# TMP37_0603.net
KiCad netlist of a schematic drawn in EAGLE
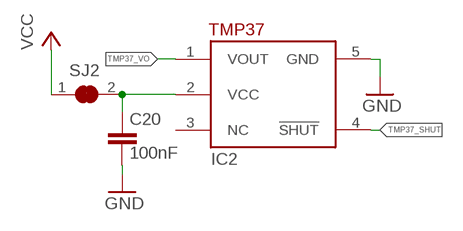
[diagram p0: schematic, sheet 1]

(export (version "E")
  (design (tool "Eeschema 10.0.6"))
  (components
    (comp (ref "C20")
      (value "100nF")
      (footprint "eagle-import:C0603")
      (libsource (lib "eagle-import") (part "C-EUC0603"))
    )
    (comp (ref "IC2")
      (value "TMP37GRTZ-REEL7")
      (footprint "eagle-import:SOT-23-5")
      (libsource (lib "eagle-import") (part "TMP37"))
    )
    (comp (ref "SJ2")
      (value "SOLDERJUMPER_CLOSED")
      (footprint "eagle-import:SOLDERJUMPER_CLOSEDWIRE")
      (libsource (lib "eagle-import") (part "SOLDERJUMPER_CLOSED"))
    )
  )
  (nets
    (net (code "1") (name "GND") (class "Default")
      (node (ref "C20") (pin "2") (pinfunction "2_2") (pintype "passive"))
      (node (ref "IC2") (pin "5") (pinfunction "GND_5") (pintype "input"))
    )
    (net (code "2") (name "Net-(IC2-VCC)") (class "Default")
      (node (ref "C20") (pin "1") (pinfunction "1_1") (pintype "passive"))
      (node (ref "IC2") (pin "2") (pinfunction "VCC_2") (pintype "power_in"))
      (node (ref "SJ2") (pin "2") (pinfunction "2_2") (pintype "passive"))
    )
    (net (code "3") (name "TMP37_SHUT") (class "Default")
      (node (ref "IC2") (pin "4") (pinfunction "~{SHUT}_4") (pintype "power_in"))
    )
    (net (code "4") (name "TMP37_VO") (class "Default")
      (node (ref "IC2") (pin "1") (pinfunction "VOUT_1") (pintype "input"))
    )
    (net (code "5") (name "VCC") (class "Default")
      (node (ref "SJ2") (pin "1") (pinfunction "1_1") (pintype "passive"))
    )
    (net (code "6") (name "unconnected-(IC2-NC-Pad3)") (class "Default")
      (node (ref "IC2") (pin "3") (pinfunction "NC_3") (pintype "bidirectional"))
    )
  )
)
